# Processor.net
KiCad netlist of a schematic drawn in Altium Designer
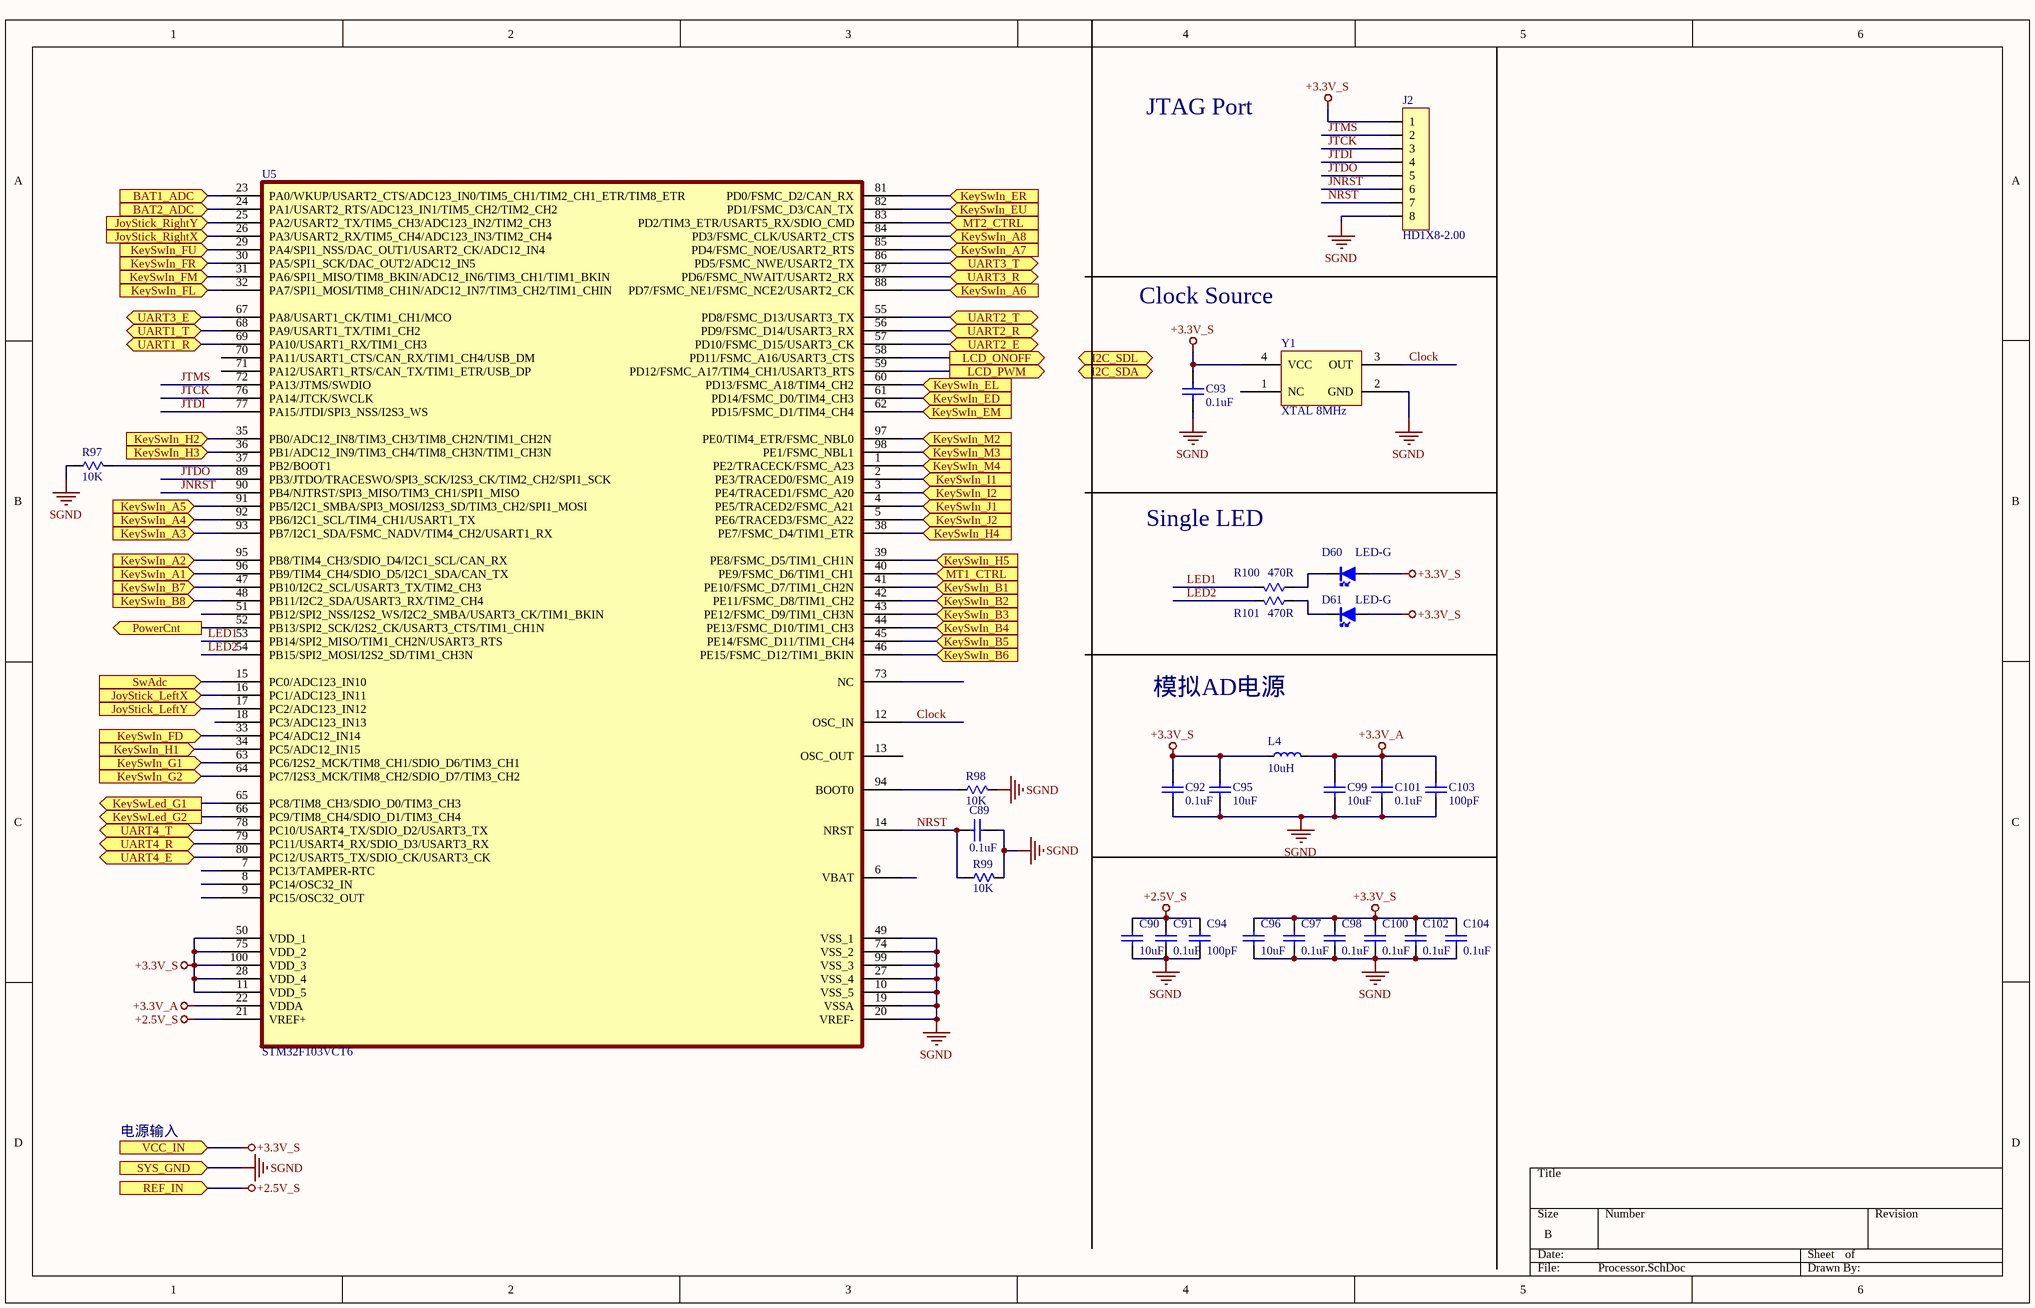
[diagram p0: Processor.SchDoc]

(export (version "E")
  (design (tool "Eeschema 10.0.6"))
  (components
    (comp (ref "C89")
      (value "0.1uF")
      (footprint "C0603")
      (description "CAP")
      (fields (field (name "PUBLISHER") "Altium Limited"))
      (libsource (lib "Passive Components Class") (part "CAP"))
    )
    (comp (ref "C90")
      (value "10uF")
      (footprint "C0805")
      (description "CAP")
      (fields (field (name "PUBLISHER") "Altium Limited"))
      (libsource (lib "Passive Components Class") (part "CAP"))
    )
    (comp (ref "C91")
      (value "0.1uF")
      (footprint "C0603")
      (description "CAP")
      (fields (field (name "PUBLISHER") "Altium Limited"))
      (libsource (lib "Passive Components Class") (part "CAP"))
    )
    (comp (ref "C92")
      (value "0.1uF")
      (footprint "C0603")
      (description "CAP")
      (fields (field (name "PUBLISHER") "Altium Limited"))
      (libsource (lib "Passive Components Class") (part "CAP"))
    )
    (comp (ref "C93")
      (value "0.1uF")
      (footprint "C0603")
      (description "Capacitor")
      (fields (field (name "PUBLISHER") "Altium Limited"))
      (libsource (lib "Miscellaneous Devices") (part "Cap"))
    )
    (comp (ref "C94")
      (value "100pF")
      (footprint "C0603")
      (description "CAP")
      (fields (field (name "PUBLISHER") "Altium Limited"))
      (libsource (lib "Passive Components Class") (part "CAP"))
    )
    (comp (ref "C95")
      (value "10uF")
      (footprint "C0805")
      (description "CAP")
      (fields (field (name "PUBLISHER") "Altium Limited"))
      (libsource (lib "Passive Components Class") (part "CAP"))
    )
    (comp (ref "C96")
      (value "10uF")
      (footprint "C0805")
      (description "CAP")
      (fields (field (name "PUBLISHER") "Altium Limited"))
      (libsource (lib "Passive Components Class") (part "CAP"))
    )
    (comp (ref "C97")
      (value "0.1uF")
      (footprint "C0603")
      (description "CAP")
      (fields (field (name "PUBLISHER") "Altium Limited"))
      (libsource (lib "Passive Components Class") (part "CAP"))
    )
    (comp (ref "C98")
      (value "0.1uF")
      (footprint "C0603")
      (description "CAP")
      (fields (field (name "PUBLISHER") "Altium Limited"))
      (libsource (lib "Passive Components Class") (part "CAP"))
    )
    (comp (ref "C99")
      (value "10uF")
      (footprint "C0805")
      (description "CAP")
      (fields (field (name "PUBLISHER") "Altium Limited"))
      (libsource (lib "Passive Components Class") (part "CAP"))
    )
    (comp (ref "C100")
      (value "0.1uF")
      (footprint "C0603")
      (description "CAP")
      (fields (field (name "PUBLISHER") "Altium Limited"))
      (libsource (lib "Passive Components Class") (part "CAP"))
    )
    (comp (ref "C101")
      (value "0.1uF")
      (footprint "C0603")
      (description "CAP")
      (fields (field (name "PUBLISHER") "Altium Limited"))
      (libsource (lib "Passive Components Class") (part "CAP"))
    )
    (comp (ref "C102")
      (value "0.1uF")
      (footprint "C0603")
      (description "CAP")
      (fields (field (name "PUBLISHER") "Altium Limited"))
      (libsource (lib "Passive Components Class") (part "CAP"))
    )
    (comp (ref "C103")
      (value "100pF")
      (footprint "C0603")
      (description "CAP")
      (fields (field (name "PUBLISHER") "Altium Limited"))
      (libsource (lib "Passive Components Class") (part "CAP"))
    )
    (comp (ref "C104")
      (value "0.1uF")
      (footprint "C0603")
      (description "CAP")
      (fields (field (name "PUBLISHER") "Altium Limited"))
      (libsource (lib "Passive Components Class") (part "CAP"))
    )
    (comp (ref "D60")
      (value "LED-G")
      (footprint "LED0805")
      (libsource (lib "Passive Components Class") (part "LED"))
    )
    (comp (ref "D61")
      (value "LED-G")
      (footprint "LED0805")
      (libsource (lib "Passive Components Class") (part "LED"))
    )
    (comp (ref "J2")
      (value "HD1X8-2.00")
      (footprint "SHD1X8-2.00")
      (libsource (lib "Connector Class") (part "HEADER1X8"))
    )
    (comp (ref "L4")
      (value "10uH")
      (footprint "L0603-C")
      (description "INDUCTOR")
      (fields (field (name "PUBLISHER") "Altium Limited"))
      (libsource (lib "Passive Components Class") (part "INDUCTOR"))
    )
    (comp (ref "R97")
      (value "10K")
      (footprint "R0603")
      (description "Resistor")
      (fields (field (name "PUBLISHER") "Altium Limited"))
      (libsource (lib "UP-Robot") (part "Res"))
    )
    (comp (ref "R98")
      (value "10K")
      (footprint "R0603")
      (description "Resistor")
      (fields (field (name "PUBLISHER") "Altium Limited"))
      (libsource (lib "UP-Robot") (part "Res"))
    )
    (comp (ref "R99")
      (value "10K")
      (footprint "R0603")
      (description "Resistor")
      (fields (field (name "PUBLISHER") "Altium Limited"))
      (libsource (lib "UP-Robot") (part "Res"))
    )
    (comp (ref "R100")
      (value "470R")
      (footprint "R0805")
      (description "Resistor")
      (fields (field (name "PUBLISHER") "Altium Limited"))
      (libsource (lib "UP-Robot") (part "Res"))
    )
    (comp (ref "R101")
      (value "470R")
      (footprint "R0805")
      (description "Resistor")
      (fields (field (name "PUBLISHER") "Altium Limited"))
      (libsource (lib "UP-Robot") (part "Res"))
    )
    (comp (ref "U5")
      (value "STM32F103VCT6")
      (footprint "STM32F103VCT6")
      (libsource (lib "Microcontrollers Class") (part "STM32F103VCT6"))
    )
    (comp (ref "Y1")
      (value "XTAL 8MHz")
      (footprint "XTAL 5.0X7.0-SM")
      (libsource (lib "Mic2805") (part "XTAL"))
    )
  )
  (nets
    (net (code "1") (name "+2.5V_S") (class "Default")
      (node (ref "C90") (pin "1") (pinfunction "1_1") (pintype "passive"))
      (node (ref "C91") (pin "1") (pinfunction "1_1") (pintype "passive"))
      (node (ref "C94") (pin "1") (pinfunction "1_1") (pintype "passive"))
      (node (ref "U5") (pin "21") (pinfunction "VREF+_21") (pintype "passive"))
    )
    (net (code "2") (name "+3.3V_A") (class "Default")
      (node (ref "C101") (pin "2") (pinfunction "2_2") (pintype "passive"))
      (node (ref "C103") (pin "2") (pinfunction "2_2") (pintype "passive"))
      (node (ref "C99") (pin "2") (pinfunction "2_2") (pintype "passive"))
      (node (ref "L4") (pin "2") (pinfunction "2_2") (pintype "passive"))
      (node (ref "U5") (pin "22") (pinfunction "VDDA_22") (pintype "passive"))
    )
    (net (code "3") (name "+3.3V_S") (class "Default")
      (node (ref "C100") (pin "1") (pinfunction "1_1") (pintype "passive"))
      (node (ref "C102") (pin "1") (pinfunction "1_1") (pintype "passive"))
      (node (ref "C104") (pin "1") (pinfunction "1_1") (pintype "passive"))
      (node (ref "C92") (pin "2") (pinfunction "2_2") (pintype "passive"))
      (node (ref "C93") (pin "2") (pinfunction "2_2") (pintype "passive"))
      (node (ref "C95") (pin "2") (pinfunction "2_2") (pintype "passive"))
      (node (ref "C96") (pin "1") (pinfunction "1_1") (pintype "passive"))
      (node (ref "C97") (pin "1") (pinfunction "1_1") (pintype "passive"))
      (node (ref "C98") (pin "1") (pinfunction "1_1") (pintype "passive"))
      (node (ref "D60") (pin "1") (pinfunction "A_1") (pintype "passive"))
      (node (ref "D61") (pin "1") (pinfunction "A_1") (pintype "passive"))
      (node (ref "J2") (pin "1") (pinfunction "1_1") (pintype "passive"))
      (node (ref "L4") (pin "1") (pinfunction "1_1") (pintype "passive"))
      (node (ref "U5") (pin "100") (pinfunction "VDD_3_100") (pintype "passive"))
      (node (ref "U5") (pin "11") (pinfunction "VDD_5_11") (pintype "passive"))
      (node (ref "U5") (pin "28") (pinfunction "VDD_4_28") (pintype "passive"))
      (node (ref "U5") (pin "50") (pinfunction "VDD_1_50") (pintype "passive"))
      (node (ref "U5") (pin "75") (pinfunction "VDD_2_75") (pintype "passive"))
      (node (ref "Y1") (pin "4") (pinfunction "VCC_4") (pintype "passive"))
    )
    (net (code "4") (name "/BAT1_ADC") (class "Default")
      (node (ref "U5") (pin "23") (pinfunction "PA0/WKUP/USART2_CTS/ADC123_IN0/TIM5_CH1/TIM2_CH1_ETR/TIM8_ETR_23") (pintype "passive"))
    )
    (net (code "5") (name "/BAT2_ADC") (class "Default")
      (node (ref "U5") (pin "24") (pinfunction "PA1/USART2_RTS/ADC123_IN1/TIM5_CH2/TIM2_CH2_24") (pintype "passive"))
    )
    (net (code "6") (name "/Clock") (class "Default")
      (node (ref "U5") (pin "12") (pinfunction "OSC_IN_12") (pintype "passive"))
      (node (ref "Y1") (pin "3") (pinfunction "OUT_3") (pintype "passive"))
    )
    (net (code "9") (name "/JNRST") (class "Default")
      (node (ref "J2") (pin "6") (pinfunction "6_6") (pintype "passive"))
      (node (ref "U5") (pin "90") (pinfunction "PB4/NJTRST/SPI3_MISO/TIM3_CH1/SPI1_MISO_90") (pintype "passive"))
    )
    (net (code "10") (name "/JTCK") (class "Default")
      (node (ref "J2") (pin "3") (pinfunction "3_3") (pintype "passive"))
      (node (ref "U5") (pin "76") (pinfunction "PA14/JTCK/SWCLK_76") (pintype "passive"))
    )
    (net (code "11") (name "/JTDI") (class "Default")
      (node (ref "J2") (pin "4") (pinfunction "4_4") (pintype "passive"))
      (node (ref "U5") (pin "77") (pinfunction "PA15/JTDI/SPI3_NSS/I2S3_WS_77") (pintype "passive"))
    )
    (net (code "12") (name "/JTDO") (class "Default")
      (node (ref "J2") (pin "5") (pinfunction "5_5") (pintype "passive"))
      (node (ref "U5") (pin "89") (pinfunction "PB3/JTDO/TRACESWO/SPI3_SCK/I2S3_CK/TIM2_CH2/SPI1_SCK_89") (pintype "passive"))
    )
    (net (code "13") (name "/JTMS") (class "Default")
      (node (ref "J2") (pin "2") (pinfunction "2_2") (pintype "passive"))
      (node (ref "U5") (pin "72") (pinfunction "PA13/JTMS/SWDIO_72") (pintype "passive"))
    )
    (net (code "14") (name "/JoyStick_LeftX") (class "Default")
      (node (ref "U5") (pin "16") (pinfunction "PC1/ADC123_IN11_16") (pintype "passive"))
    )
    (net (code "15") (name "/JoyStick_LeftY") (class "Default")
      (node (ref "U5") (pin "17") (pinfunction "PC2/ADC123_IN12_17") (pintype "passive"))
    )
    (net (code "16") (name "/JoyStick_RightX") (class "Default")
      (node (ref "U5") (pin "26") (pinfunction "PA3/USART2_RX/TIM5_CH4/ADC123_IN3/TIM2_CH4_26") (pintype "passive"))
    )
    (net (code "17") (name "/JoyStick_RightY") (class "Default")
      (node (ref "U5") (pin "25") (pinfunction "PA2/USART2_TX/TIM5_CH3/ADC123_IN2/TIM2_CH3_25") (pintype "passive"))
    )
    (net (code "18") (name "/KeySwIn_A1") (class "Default")
      (node (ref "U5") (pin "96") (pinfunction "PB9/TIM4_CH4/SDIO_D5/I2C1_SDA/CAN_TX_96") (pintype "passive"))
    )
    (net (code "19") (name "/KeySwIn_A2") (class "Default")
      (node (ref "U5") (pin "95") (pinfunction "PB8/TIM4_CH3/SDIO_D4/I2C1_SCL/CAN_RX_95") (pintype "passive"))
    )
    (net (code "20") (name "/KeySwIn_A3") (class "Default")
      (node (ref "U5") (pin "93") (pinfunction "PB7/I2C1_SDA/FSMC_NADV/TIM4_CH2/USART1_RX_93") (pintype "passive"))
    )
    (net (code "21") (name "/KeySwIn_A4") (class "Default")
      (node (ref "U5") (pin "92") (pinfunction "PB6/I2C1_SCL/TIM4_CH1/USART1_TX_92") (pintype "passive"))
    )
    (net (code "22") (name "/KeySwIn_A5") (class "Default")
      (node (ref "U5") (pin "91") (pinfunction "PB5/I2C1_SMBA/SPI3_MOSI/I2S3_SD/TIM3_CH2/SPI1_MOSI_91") (pintype "passive"))
    )
    (net (code "23") (name "/KeySwIn_A6") (class "Default")
      (node (ref "U5") (pin "88") (pinfunction "PD7/FSMC_NE1/FSMC_NCE2/USART2_CK_88") (pintype "passive"))
    )
    (net (code "24") (name "/KeySwIn_A7") (class "Default")
      (node (ref "U5") (pin "85") (pinfunction "PD4/FSMC_NOE/USART2_RTS_85") (pintype "passive"))
    )
    (net (code "25") (name "/KeySwIn_A8") (class "Default")
      (node (ref "U5") (pin "84") (pinfunction "PD3/FSMC_CLK/USART2_CTS_84") (pintype "passive"))
    )
    (net (code "26") (name "/KeySwIn_B1") (class "Default")
      (node (ref "U5") (pin "41") (pinfunction "PE10/FSMC_D7/TIM1_CH2N_41") (pintype "passive"))
    )
    (net (code "27") (name "/KeySwIn_B2") (class "Default")
      (node (ref "U5") (pin "42") (pinfunction "PE11/FSMC_D8/TIM1_CH2_42") (pintype "passive"))
    )
    (net (code "28") (name "/KeySwIn_B3") (class "Default")
      (node (ref "U5") (pin "43") (pinfunction "PE12/FSMC_D9/TIM1_CH3N_43") (pintype "passive"))
    )
    (net (code "29") (name "/KeySwIn_B4") (class "Default")
      (node (ref "U5") (pin "44") (pinfunction "PE13/FSMC_D10/TIM1_CH3_44") (pintype "passive"))
    )
    (net (code "30") (name "/KeySwIn_B5") (class "Default")
      (node (ref "U5") (pin "45") (pinfunction "PE14/FSMC_D11/TIM1_CH4_45") (pintype "passive"))
    )
    (net (code "31") (name "/KeySwIn_B6") (class "Default")
      (node (ref "U5") (pin "46") (pinfunction "PE15/FSMC_D12/TIM1_BKIN_46") (pintype "passive"))
    )
    (net (code "32") (name "/KeySwIn_B7") (class "Default")
      (node (ref "U5") (pin "47") (pinfunction "PB10/I2C2_SCL/USART3_TX/TIM2_CH3_47") (pintype "passive"))
    )
    (net (code "33") (name "/KeySwIn_B8") (class "Default")
      (node (ref "U5") (pin "48") (pinfunction "PB11/I2C2_SDA/USART3_RX/TIM2_CH4_48") (pintype "passive"))
    )
    (net (code "34") (name "/KeySwIn_ED") (class "Default")
      (node (ref "U5") (pin "61") (pinfunction "PD14/FSMC_D0/TIM4_CH3_61") (pintype "passive"))
    )
    (net (code "35") (name "/KeySwIn_EL") (class "Default")
      (node (ref "U5") (pin "60") (pinfunction "PD13/FSMC_A18/TIM4_CH2_60") (pintype "passive"))
    )
    (net (code "36") (name "/KeySwIn_EM") (class "Default")
      (node (ref "U5") (pin "62") (pinfunction "PD15/FSMC_D1/TIM4_CH4_62") (pintype "passive"))
    )
    (net (code "37") (name "/KeySwIn_ER") (class "Default")
      (node (ref "U5") (pin "81") (pinfunction "PD0/FSMC_D2/CAN_RX_81") (pintype "passive"))
    )
    (net (code "38") (name "/KeySwIn_EU") (class "Default")
      (node (ref "U5") (pin "82") (pinfunction "PD1/FSMC_D3/CAN_TX_82") (pintype "passive"))
    )
    (net (code "39") (name "/KeySwIn_FD") (class "Default")
      (node (ref "U5") (pin "33") (pinfunction "PC4/ADC12_IN14_33") (pintype "passive"))
    )
    (net (code "40") (name "/KeySwIn_FL") (class "Default")
      (node (ref "U5") (pin "32") (pinfunction "PA7/SPI1_MOSI/TIM8_CH1N/ADC12_IN7/TIM3_CH2/TIM1_CHIN_32") (pintype "passive"))
    )
    (net (code "41") (name "/KeySwIn_FM") (class "Default")
      (node (ref "U5") (pin "31") (pinfunction "PA6/SPI1_MISO/TIM8_BKIN/ADC12_IN6/TIM3_CH1/TIM1_BKIN_31") (pintype "passive"))
    )
    (net (code "42") (name "/KeySwIn_FR") (class "Default")
      (node (ref "U5") (pin "30") (pinfunction "PA5/SPI1_SCK/DAC_OUT2/ADC12_IN5_30") (pintype "passive"))
    )
    (net (code "43") (name "/KeySwIn_FU") (class "Default")
      (node (ref "U5") (pin "29") (pinfunction "PA4/SPI1_NSS/DAC_OUT1/USART2_CK/ADC12_IN4_29") (pintype "passive"))
    )
    (net (code "44") (name "/KeySwIn_G1") (class "Default")
      (node (ref "U5") (pin "63") (pinfunction "PC6/I2S2_MCK/TIM8_CH1/SDIO_D6/TIM3_CH1_63") (pintype "passive"))
    )
    (net (code "45") (name "/KeySwIn_G2") (class "Default")
      (node (ref "U5") (pin "64") (pinfunction "PC7/I2S3_MCK/TIM8_CH2/SDIO_D7/TIM3_CH2_64") (pintype "passive"))
    )
    (net (code "46") (name "/KeySwIn_H1") (class "Default")
      (node (ref "U5") (pin "34") (pinfunction "PC5/ADC12_IN15_34") (pintype "passive"))
    )
    (net (code "47") (name "/KeySwIn_H2") (class "Default")
      (node (ref "U5") (pin "35") (pinfunction "PB0/ADC12_IN8/TIM3_CH3/TIM8_CH2N/TIM1_CH2N_35") (pintype "passive"))
    )
    (net (code "48") (name "/KeySwIn_H3") (class "Default")
      (node (ref "U5") (pin "36") (pinfunction "PB1/ADC12_IN9/TIM3_CH4/TIM8_CH3N/TIM1_CH3N_36") (pintype "passive"))
    )
    (net (code "49") (name "/KeySwIn_H4") (class "Default")
      (node (ref "U5") (pin "38") (pinfunction "PE7/FSMC_D4/TIM1_ETR_38") (pintype "passive"))
    )
    (net (code "50") (name "/KeySwIn_H5") (class "Default")
      (node (ref "U5") (pin "39") (pinfunction "PE8/FSMC_D5/TIM1_CH1N_39") (pintype "passive"))
    )
    (net (code "51") (name "/KeySwIn_I1") (class "Default")
      (node (ref "U5") (pin "2") (pinfunction "PE3/TRACED0/FSMC_A19_2") (pintype "passive"))
    )
    (net (code "52") (name "/KeySwIn_I2") (class "Default")
      (node (ref "U5") (pin "3") (pinfunction "PE4/TRACED1/FSMC_A20_3") (pintype "passive"))
    )
    (net (code "53") (name "/KeySwIn_J1") (class "Default")
      (node (ref "U5") (pin "4") (pinfunction "PE5/TRACED2/FSMC_A21_4") (pintype "passive"))
    )
    (net (code "54") (name "/KeySwIn_J2") (class "Default")
      (node (ref "U5") (pin "5") (pinfunction "PE6/TRACED3/FSMC_A22_5") (pintype "passive"))
    )
    (net (code "55") (name "/KeySwIn_M2") (class "Default")
      (node (ref "U5") (pin "97") (pinfunction "PE0/TIM4_ETR/FSMC_NBL0_97") (pintype "passive"))
    )
    (net (code "56") (name "/KeySwIn_M3") (class "Default")
      (node (ref "U5") (pin "98") (pinfunction "PE1/FSMC_NBL1_98") (pintype "passive"))
    )
    (net (code "57") (name "/KeySwIn_M4") (class "Default")
      (node (ref "U5") (pin "1") (pinfunction "PE2/TRACECK/FSMC_A23_1") (pintype "passive"))
    )
    (net (code "58") (name "/KeySwLed_G1") (class "Default")
      (node (ref "U5") (pin "65") (pinfunction "PC8/TIM8_CH3/SDIO_D0/TIM3_CH3_65") (pintype "passive"))
    )
    (net (code "59") (name "/KeySwLed_G2") (class "Default")
      (node (ref "U5") (pin "66") (pinfunction "PC9/TIM8_CH4/SDIO_D1/TIM3_CH4_66") (pintype "passive"))
    )
    (net (code "60") (name "/LCD_ONOFF") (class "Default")
      (node (ref "U5") (pin "58") (pinfunction "PD11/FSMC_A16/USART3_CTS_58") (pintype "passive"))
    )
    (net (code "61") (name "/LCD_PWM") (class "Default")
      (node (ref "U5") (pin "59") (pinfunction "PD12/FSMC_A17/TIM4_CH1/USART3_RTS_59") (pintype "passive"))
    )
    (net (code "62") (name "/LED1") (class "Default")
      (node (ref "R100") (pin "1") (pinfunction "1_1") (pintype "passive"))
      (node (ref "U5") (pin "53") (pinfunction "PB14/SPI2_MISO/TIM1_CH2N/USART3_RTS_53") (pintype "passive"))
    )
    (net (code "63") (name "/LED2") (class "Default")
      (node (ref "R101") (pin "1") (pinfunction "1_1") (pintype "passive"))
      (node (ref "U5") (pin "54") (pinfunction "PB15/SPI2_MOSI/I2S2_SD/TIM1_CH3N_54") (pintype "passive"))
    )
    (net (code "64") (name "/MT1_CTRL") (class "Default")
      (node (ref "U5") (pin "40") (pinfunction "PE9/FSMC_D6/TIM1_CH1_40") (pintype "passive"))
    )
    (net (code "65") (name "/MT2_CTRL") (class "Default")
      (node (ref "U5") (pin "83") (pinfunction "PD2/TIM3_ETR/USART5_RX/SDIO_CMD_83") (pintype "passive"))
    )
    (net (code "66") (name "/NRST") (class "Default")
      (node (ref "C89") (pin "1") (pinfunction "1_1") (pintype "passive"))
      (node (ref "J2") (pin "7") (pinfunction "7_7") (pintype "passive"))
      (node (ref "R99") (pin "2") (pinfunction "2_2") (pintype "passive"))
      (node (ref "U5") (pin "14") (pinfunction "NRST_14") (pintype "passive"))
    )
    (net (code "67") (name "/PowerCnt") (class "Default")
      (node (ref "U5") (pin "52") (pinfunction "PB13/SPI2_SCK/I2S2_CK/USART3_CTS/TIM1_CH1N_52") (pintype "passive"))
    )
    (net (code "68") (name "/SwAdc") (class "Default")
      (node (ref "U5") (pin "15") (pinfunction "PC0/ADC123_IN10_15") (pintype "passive"))
    )
    (net (code "69") (name "/UART1_R") (class "Default")
      (node (ref "U5") (pin "69") (pinfunction "PA10/USART1_RX/TIM1_CH3_69") (pintype "passive"))
    )
    (net (code "70") (name "/UART1_T") (class "Default")
      (node (ref "U5") (pin "68") (pinfunction "PA9/USART1_TX/TIM1_CH2_68") (pintype "passive"))
    )
    (net (code "71") (name "/UART2_E") (class "Default")
      (node (ref "U5") (pin "57") (pinfunction "PD10/FSMC_D15/USART3_CK_57") (pintype "passive"))
    )
    (net (code "72") (name "/UART2_R") (class "Default")
      (node (ref "U5") (pin "56") (pinfunction "PD9/FSMC_D14/USART3_RX_56") (pintype "passive"))
    )
    (net (code "73") (name "/UART2_T") (class "Default")
      (node (ref "U5") (pin "55") (pinfunction "PD8/FSMC_D13/USART3_TX_55") (pintype "passive"))
    )
    (net (code "74") (name "/UART3_E") (class "Default")
      (node (ref "U5") (pin "67") (pinfunction "PA8/USART1_CK/TIM1_CH1/MCO_67") (pintype "passive"))
    )
    (net (code "75") (name "/UART3_R") (class "Default")
      (node (ref "U5") (pin "87") (pinfunction "PD6/FSMC_NWAIT/USART2_RX_87") (pintype "passive"))
    )
    (net (code "76") (name "/UART3_T") (class "Default")
      (node (ref "U5") (pin "86") (pinfunction "PD5/FSMC_NWE/USART2_TX_86") (pintype "passive"))
    )
    (net (code "77") (name "/UART4_E") (class "Default")
      (node (ref "U5") (pin "80") (pinfunction "PC12/USART5_TX/SDIO_CK/USART3_CK_80") (pintype "passive"))
    )
    (net (code "78") (name "/UART4_R") (class "Default")
      (node (ref "U5") (pin "79") (pinfunction "PC11/USART4_RX/SDIO_D3/USART3_RX_79") (pintype "passive"))
    )
    (net (code "79") (name "/UART4_T") (class "Default")
      (node (ref "U5") (pin "78") (pinfunction "PC10/USART4_TX/SDIO_D2/USART3_TX_78") (pintype "passive"))
    )
    (net (code "80") (name "Net-(D60-K)") (class "Default")
      (node (ref "D60") (pin "2") (pinfunction "K_2") (pintype "passive"))
      (node (ref "R100") (pin "2") (pinfunction "2_2") (pintype "passive"))
    )
    (net (code "81") (name "Net-(D61-K)") (class "Default")
      (node (ref "D61") (pin "2") (pinfunction "K_2") (pintype "passive"))
      (node (ref "R101") (pin "2") (pinfunction "2_2") (pintype "passive"))
    )
    (net (code "82") (name "Net-(U5-BOOT0)") (class "Default")
      (node (ref "R98") (pin "2") (pinfunction "2_2") (pintype "passive"))
      (node (ref "U5") (pin "94") (pinfunction "BOOT0_94") (pintype "passive"))
    )
    (net (code "83") (name "Net-(U5-PB2{slash}BOOT1)") (class "Default")
      (node (ref "R97") (pin "1") (pinfunction "1_1") (pintype "passive"))
      (node (ref "U5") (pin "37") (pinfunction "PB2/BOOT1_37") (pintype "passive"))
    )
    (net (code "84") (name "SGND") (class "Default")
      (node (ref "C100") (pin "2") (pinfunction "2_2") (pintype "passive"))
      (node (ref "C101") (pin "1") (pinfunction "1_1") (pintype "passive"))
      (node (ref "C102") (pin "2") (pinfunction "2_2") (pintype "passive"))
      (node (ref "C103") (pin "1") (pinfunction "1_1") (pintype "passive"))
      (node (ref "C104") (pin "2") (pinfunction "2_2") (pintype "passive"))
      (node (ref "C89") (pin "2") (pinfunction "2_2") (pintype "passive"))
      (node (ref "C90") (pin "2") (pinfunction "2_2") (pintype "passive"))
      (node (ref "C91") (pin "2") (pinfunction "2_2") (pintype "passive"))
      (node (ref "C92") (pin "1") (pinfunction "1_1") (pintype "passive"))
      (node (ref "C93") (pin "1") (pinfunction "1_1") (pintype "passive"))
      (node (ref "C94") (pin "2") (pinfunction "2_2") (pintype "passive"))
      (node (ref "C95") (pin "1") (pinfunction "1_1") (pintype "passive"))
      (node (ref "C96") (pin "2") (pinfunction "2_2") (pintype "passive"))
      (node (ref "C97") (pin "2") (pinfunction "2_2") (pintype "passive"))
      (node (ref "C98") (pin "2") (pinfunction "2_2") (pintype "passive"))
      (node (ref "C99") (pin "1") (pinfunction "1_1") (pintype "passive"))
      (node (ref "J2") (pin "8") (pinfunction "8_8") (pintype "passive"))
      (node (ref "R97") (pin "2") (pinfunction "2_2") (pintype "passive"))
      (node (ref "R98") (pin "1") (pinfunction "1_1") (pintype "passive"))
      (node (ref "R99") (pin "1") (pinfunction "1_1") (pintype "passive"))
      (node (ref "U5") (pin "10") (pinfunction "VSS_5_10") (pintype "passive"))
      (node (ref "U5") (pin "19") (pinfunction "VSSA_19") (pintype "passive"))
      (node (ref "U5") (pin "20") (pinfunction "VREF-_20") (pintype "passive"))
      (node (ref "U5") (pin "27") (pinfunction "VSS_4_27") (pintype "passive"))
      (node (ref "U5") (pin "49") (pinfunction "VSS_1_49") (pintype "passive"))
      (node (ref "U5") (pin "74") (pinfunction "VSS_2_74") (pintype "passive"))
      (node (ref "U5") (pin "99") (pinfunction "VSS_3_99") (pintype "passive"))
      (node (ref "Y1") (pin "2") (pinfunction "GND_2") (pintype "passive"))
    )
    (net (code "85") (name "unconnected-(U5-NC-Pad73)") (class "Default")
      (node (ref "U5") (pin "73") (pinfunction "NC_73") (pintype "passive"))
    )
    (net (code "86") (name "unconnected-(U5-OSC_OUT-Pad13)") (class "Default")
      (node (ref "U5") (pin "13") (pinfunction "OSC_OUT_13") (pintype "passive"))
    )
    (net (code "87") (name "unconnected-(U5-PA11{slash}USART1_CTS{slash}CAN_RX{slash}TIM1_CH4{slash}USB_DM-Pad70)") (class "Default")
      (node (ref "U5") (pin "70") (pinfunction "PA11/USART1_CTS/CAN_RX/TIM1_CH4/USB_DM_70") (pintype "passive"))
    )
    (net (code "88") (name "unconnected-(U5-PA12{slash}USART1_RTS{slash}CAN_TX{slash}TIM1_ETR{slash}USB_DP-Pad71)") (class "Default")
      (node (ref "U5") (pin "71") (pinfunction "PA12/USART1_RTS/CAN_TX/TIM1_ETR/USB_DP_71") (pintype "passive"))
    )
    (net (code "89") (name "unconnected-(U5-PB12{slash}SPI2_NSS{slash}I2S2_WS{slash}I2C2_SMBA{slash}USART3_CK{slash}TIM1_BKIN-Pad51)") (class "Default")
      (node (ref "U5") (pin "51") (pinfunction "PB12/SPI2_NSS/I2S2_WS/I2C2_SMBA/USART3_CK/TIM1_BKIN_51") (pintype "passive"))
    )
    (net (code "90") (name "unconnected-(U5-PC3{slash}ADC123_IN13-Pad18)") (class "Default")
      (node (ref "U5") (pin "18") (pinfunction "PC3/ADC123_IN13_18") (pintype "passive"))
    )
    (net (code "91") (name "unconnected-(U5-PC13{slash}TAMPER-RTC-Pad7)") (class "Default")
      (node (ref "U5") (pin "7") (pinfunction "PC13/TAMPER-RTC_7") (pintype "passive"))
    )
    (net (code "92") (name "unconnected-(U5-PC14{slash}OSC32_IN-Pad8)") (class "Default")
      (node (ref "U5") (pin "8") (pinfunction "PC14/OSC32_IN_8") (pintype "passive"))
    )
    (net (code "93") (name "unconnected-(U5-PC15{slash}OSC32_OUT-Pad9)") (class "Default")
      (node (ref "U5") (pin "9") (pinfunction "PC15/OSC32_OUT_9") (pintype "passive"))
    )
    (net (code "94") (name "unconnected-(U5-VBAT-Pad6)") (class "Default")
      (node (ref "U5") (pin "6") (pinfunction "VBAT_6") (pintype "passive"))
    )
    (net (code "95") (name "unconnected-(Y1-NC-Pad1)") (class "Default")
      (node (ref "Y1") (pin "1") (pinfunction "NC_1") (pintype "passive"))
    )
  )
)
